# midipal-v03.net
KiCad netlist of a schematic drawn in EAGLE
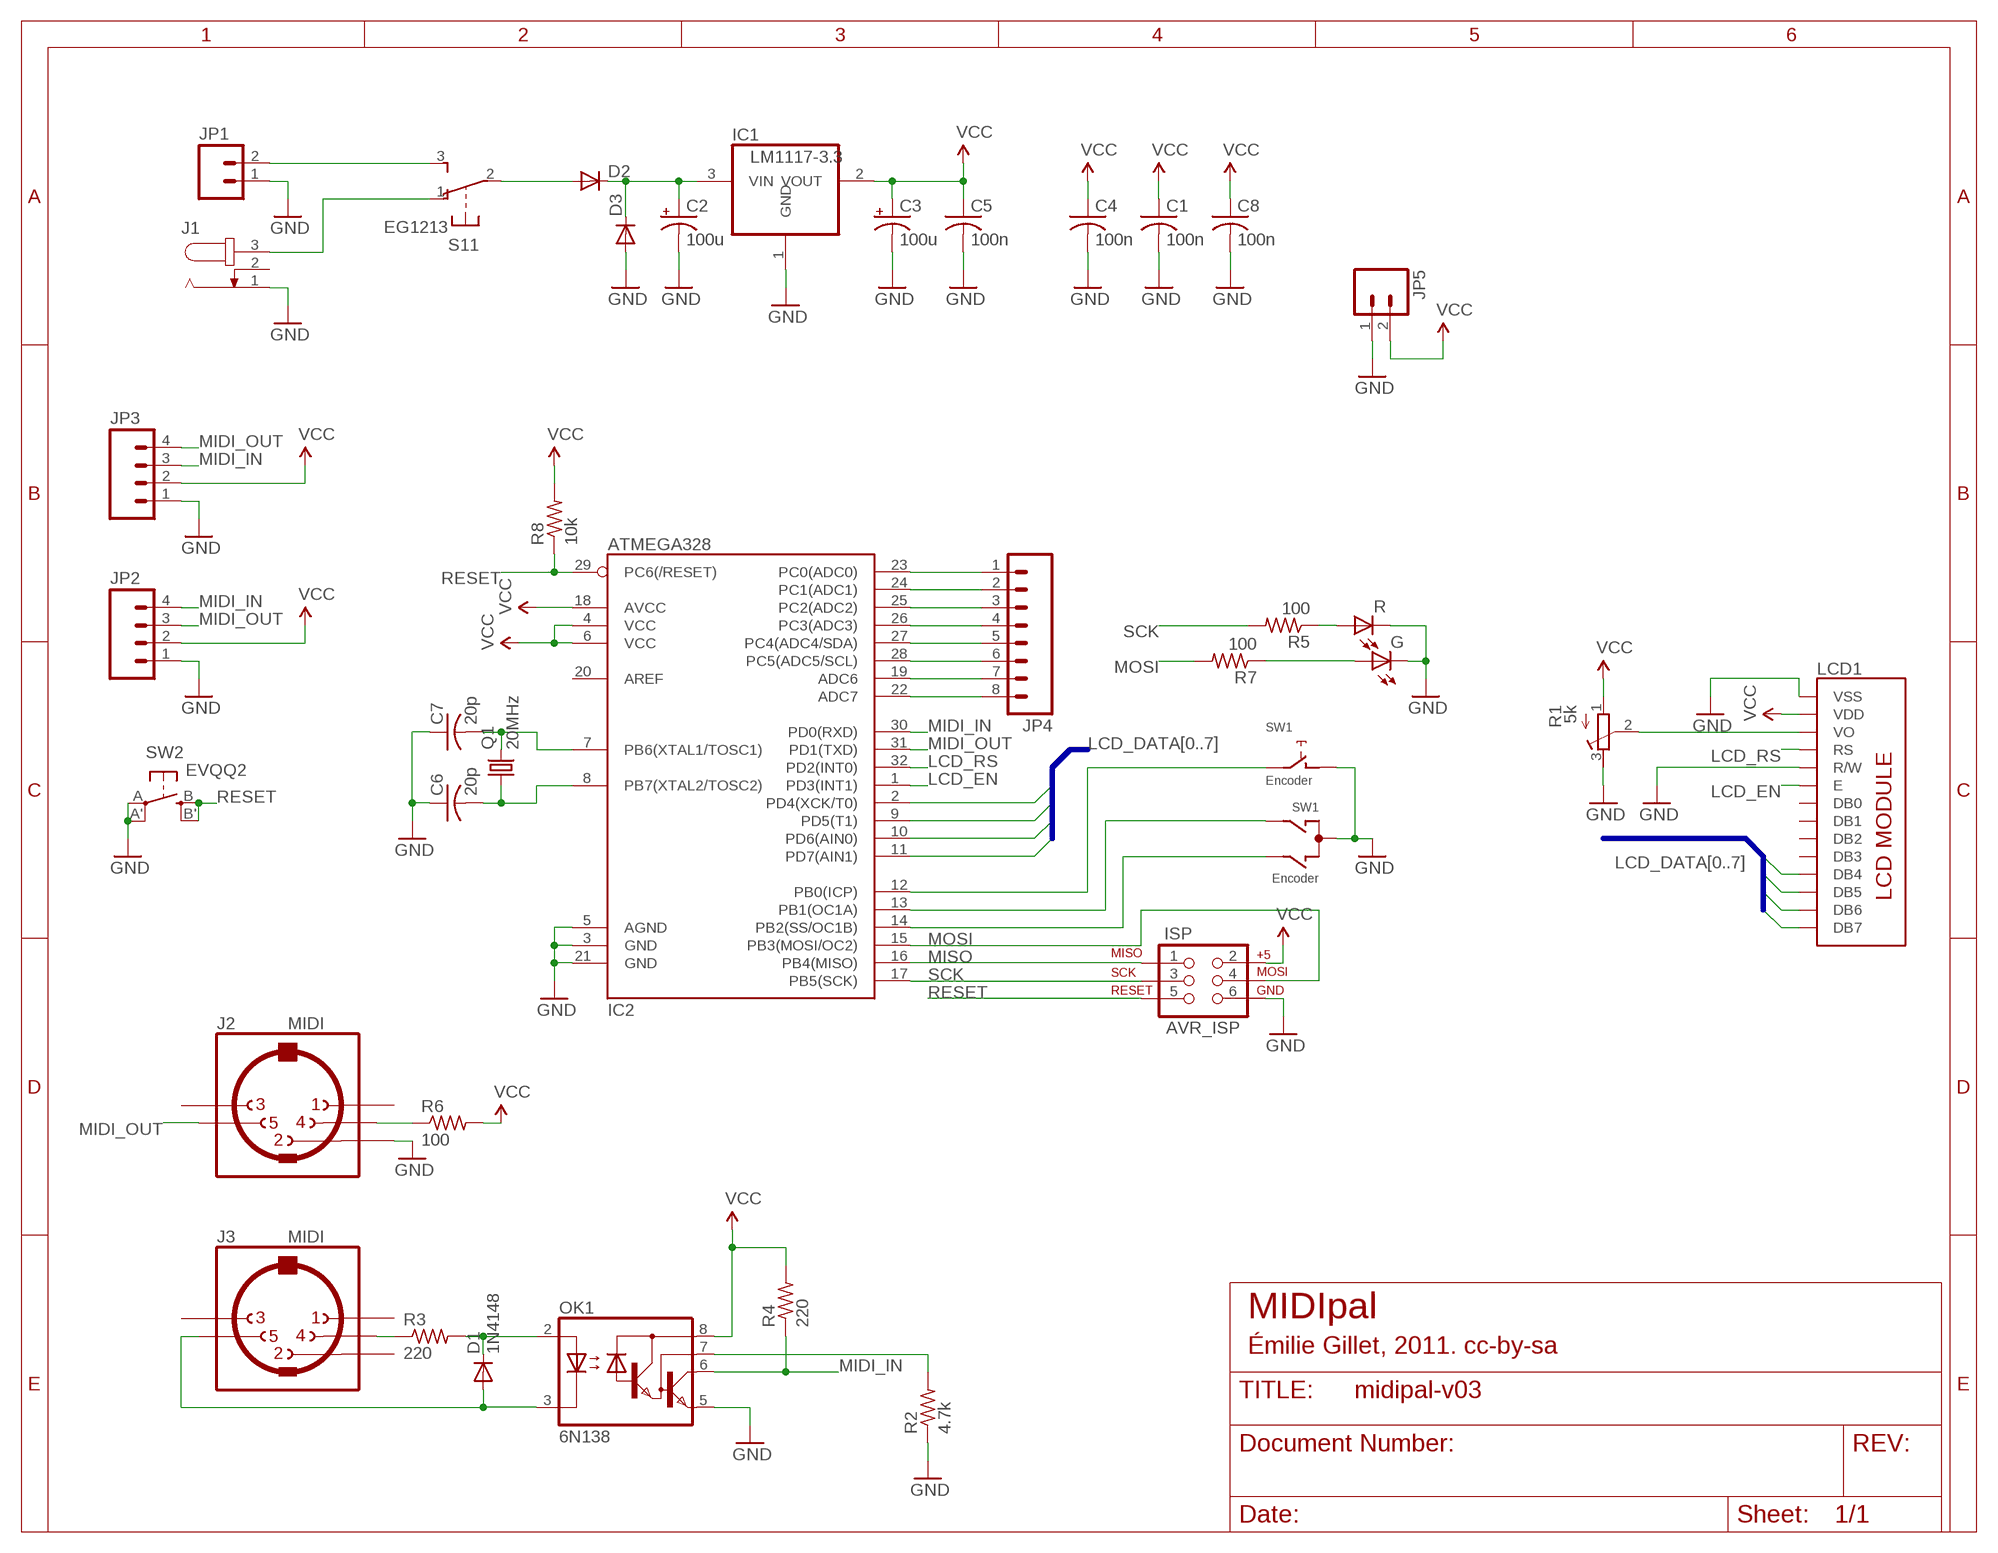
[diagram p0: schematic, sheet 1]

(export (version "E")
  (design (tool "Eeschema 10.0.6"))
  (components
    (comp (ref "C1")
      (value "100n")
      (footprint "eagle-import:C0805")
      (libsource (lib "eagle-import") (part "C-USC0805"))
    )
    (comp (ref "C2")
      (value "100u")
      (footprint "eagle-import:PANASONIC_D")
      (libsource (lib "eagle-import") (part "CPOL-USD"))
    )
    (comp (ref "C3")
      (value "100u")
      (footprint "eagle-import:PANASONIC_D")
      (libsource (lib "eagle-import") (part "CPOL-USD"))
    )
    (comp (ref "C4")
      (value "100n")
      (footprint "eagle-import:C0805")
      (libsource (lib "eagle-import") (part "C-USC0805"))
    )
    (comp (ref "C5")
      (value "100n")
      (footprint "eagle-import:C0805")
      (libsource (lib "eagle-import") (part "C-USC0805"))
    )
    (comp (ref "C6")
      (value "20p")
      (footprint "eagle-import:C0805")
      (libsource (lib "eagle-import") (part "C-USC0805"))
    )
    (comp (ref "C7")
      (value "20p")
      (footprint "eagle-import:C0805")
      (libsource (lib "eagle-import") (part "C-USC0805"))
    )
    (comp (ref "C8")
      (value "100n")
      (footprint "eagle-import:C0805")
      (libsource (lib "eagle-import") (part "C-USC0805"))
    )
    (comp (ref "D1")
      (value "1N4148")
      (footprint "eagle-import:SOD323-W")
      (libsource (lib "eagle-import") (part "DIODE-SOD323-W"))
    )
    (comp (ref "D2")
      (value "DIODESMB")
      (footprint "eagle-import:SMB-DIODE")
      (libsource (lib "eagle-import") (part "DIODESMB"))
    )
    (comp (ref "D3")
      (value "DIODESMB")
      (footprint "eagle-import:SMB-DIODE")
      (libsource (lib "eagle-import") (part "DIODESMB"))
    )
    (comp (ref "G")
      (value "LEDCHIPLED_1206")
      (footprint "eagle-import:CHIPLED_1206")
      (libsource (lib "eagle-import") (part "LEDCHIPLED_1206"))
    )
    (comp (ref "IC1")
      (value "LM1117-3.3")
      (footprint "eagle-import:SOT223")
      (libsource (lib "eagle-import") (part "REG1117"))
    )
    (comp (ref "IC2")
      (value "ATMEGA328")
      (footprint "eagle-import:TQFP32-08")
      (libsource (lib "eagle-import") (part "ATMEGA168"))
    )
    (comp (ref "ISP")
      (value "AVR_ISP")
      (footprint "eagle-import:2X3")
      (libsource (lib "eagle-import") (part "AVR_SPI_PRG_6PTH"))
    )
    (comp (ref "J1")
      (value "JACK-PLUG2")
      (footprint "eagle-import:SPC4078_BIG_HOLES")
      (libsource (lib "eagle-import") (part "JACK-PLUG2"))
    )
    (comp (ref "J2")
      (value "MIDI")
      (footprint "eagle-import:MAB5SH")
      (libsource (lib "eagle-import") (part "MAB5SH"))
    )
    (comp (ref "J3")
      (value "MIDI")
      (footprint "eagle-import:MAB5SH")
      (libsource (lib "eagle-import") (part "MAB5SH"))
    )
    (comp (ref "JP1")
      (value "M02")
      (footprint "eagle-import:1X02_LONGPADS")
      (libsource (lib "eagle-import") (part "M02"))
    )
    (comp (ref "JP2")
      (value "M04PTH")
      (footprint "eagle-import:1X04")
      (libsource (lib "eagle-import") (part "M04PTH"))
    )
    (comp (ref "JP3")
      (value "M04PTH")
      (footprint "eagle-import:1X04")
      (libsource (lib "eagle-import") (part "M04PTH"))
    )
    (comp (ref "JP4")
      (value "M08")
      (footprint "eagle-import:1X08")
      (libsource (lib "eagle-import") (part "M08"))
    )
    (comp (ref "JP5")
      (value "M02PTH")
      (footprint "eagle-import:1X02")
      (libsource (lib "eagle-import") (part "M02PTH"))
    )
    (comp (ref "LCD1")
      (value "LCD_MODULE_NO_BKL")
      (footprint "eagle-import:LCD_MODULE_1X8")
      (libsource (lib "eagle-import") (part "LCD_MODULE_NO_BKL"))
    )
    (comp (ref "OK1")
      (value "6N138")
      (footprint "eagle-import:DIL8-SMD")
      (libsource (lib "eagle-import") (part "6N138SMD8"))
    )
    (comp (ref "Q1")
      (value "20MHz")
      (footprint "eagle-import:HC49UP")
      (libsource (lib "eagle-import") (part "CRYSTALHC49UP"))
    )
    (comp (ref "R")
      (value "LEDCHIPLED_1206")
      (footprint "eagle-import:CHIPLED_1206")
      (libsource (lib "eagle-import") (part "LEDCHIPLED_1206"))
    )
    (comp (ref "R1")
      (value "5k")
      (footprint "eagle-import:RTRIM3296P")
      (libsource (lib "eagle-import") (part "R-TRIMM3296P"))
    )
    (comp (ref "R2")
      (value "4.7k")
      (footprint "eagle-import:M0805")
      (libsource (lib "eagle-import") (part "R-US_M0805"))
    )
    (comp (ref "R3")
      (value "220")
      (footprint "eagle-import:M0805")
      (libsource (lib "eagle-import") (part "R-US_M0805"))
    )
    (comp (ref "R4")
      (value "220")
      (footprint "eagle-import:R0805")
      (libsource (lib "eagle-import") (part "R-US_R0805"))
    )
    (comp (ref "R5")
      (value "100")
      (footprint "eagle-import:R0805")
      (libsource (lib "eagle-import") (part "R-US_R0805"))
    )
    (comp (ref "R6")
      (value "100")
      (footprint "eagle-import:R0805")
      (libsource (lib "eagle-import") (part "R-US_R0805"))
    )
    (comp (ref "R7")
      (value "100")
      (footprint "eagle-import:R0805")
      (libsource (lib "eagle-import") (part "R-US_R0805"))
    )
    (comp (ref "R8")
      (value "10k")
      (footprint "eagle-import:R0805")
      (libsource (lib "eagle-import") (part "R-US_R0805"))
    )
    (comp (ref "S1")
      (value "EG1213")
      (footprint "eagle-import:EG1213")
      (libsource (lib "eagle-import") (part "EG1213"))
    )
    (comp (ref "SW1")
      (value "Encoder")
      (footprint "eagle-import:ALPS_EC12E_SW")
      (libsource (lib "eagle-import") (part "EC12E_SW"))
    )
    (comp (ref "SW2")
      (value "EVQQ2")
      (footprint "eagle-import:EVQ-Q2")
      (libsource (lib "eagle-import") (part "EVQQ2"))
    )
  )
  (nets
    (net (code "5") (name "/LCD_DATA4") (class "Default")
      (node (ref "IC2") (pin "2") (pinfunction "PD4(XCK/T0)_2") (pintype "bidirectional"))
      (node (ref "LCD1") (pin "11") (pinfunction "DB4_11") (pintype "bidirectional"))
    )
    (net (code "6") (name "/LCD_DATA5") (class "Default")
      (node (ref "IC2") (pin "9") (pinfunction "PD5(T1)_9") (pintype "bidirectional"))
      (node (ref "LCD1") (pin "12") (pinfunction "DB5_12") (pintype "bidirectional"))
    )
    (net (code "7") (name "/LCD_DATA6") (class "Default")
      (node (ref "IC2") (pin "10") (pinfunction "PD6(AIN0)_10") (pintype "bidirectional"))
      (node (ref "LCD1") (pin "13") (pinfunction "DB6_13") (pintype "bidirectional"))
    )
    (net (code "8") (name "/LCD_DATA7") (class "Default")
      (node (ref "IC2") (pin "11") (pinfunction "PD7(AIN1)_11") (pintype "bidirectional"))
      (node (ref "LCD1") (pin "14") (pinfunction "DB7_14") (pintype "bidirectional"))
    )
    (net (code "10") (name "/LCD_EN") (class "Default")
      (node (ref "IC2") (pin "1") (pinfunction "PD3(INT1)_1") (pintype "bidirectional"))
      (node (ref "LCD1") (pin "6") (pinfunction "E_6") (pintype "input"))
    )
    (net (code "11") (name "/LCD_RS") (class "Default")
      (node (ref "IC2") (pin "32") (pinfunction "PD2(INT0)_32") (pintype "bidirectional"))
      (node (ref "LCD1") (pin "4") (pinfunction "RS_4") (pintype "input"))
    )
    (net (code "12") (name "/MIDI_IN") (class "Default")
      (node (ref "IC2") (pin "30") (pinfunction "PD0(RXD)_30") (pintype "bidirectional"))
      (node (ref "JP2") (pin "4") (pinfunction "4_4") (pintype "passive"))
      (node (ref "JP3") (pin "3") (pinfunction "3_3") (pintype "passive"))
      (node (ref "OK1") (pin "6") (pinfunction "VO_6") (pintype "passive"))
      (node (ref "R4") (pin "1") (pinfunction "1_1") (pintype "passive"))
    )
    (net (code "13") (name "/MIDI_OUT") (class "Default")
      (node (ref "IC2") (pin "31") (pinfunction "PD1(TXD)_31") (pintype "bidirectional"))
      (node (ref "J2") (pin "5") (pinfunction "5_5") (pintype "passive"))
      (node (ref "JP2") (pin "3") (pinfunction "3_3") (pintype "passive"))
      (node (ref "JP3") (pin "4") (pinfunction "4_4") (pintype "passive"))
    )
    (net (code "14") (name "/MISO") (class "Default")
      (node (ref "IC2") (pin "16") (pinfunction "PB4(MISO)_16") (pintype "bidirectional"))
      (node (ref "ISP") (pin "1") (pinfunction "1_1") (pintype "passive"))
    )
    (net (code "15") (name "/MOSI") (class "Default")
      (node (ref "IC2") (pin "15") (pinfunction "PB3(MOSI/OC2)_15") (pintype "bidirectional"))
      (node (ref "ISP") (pin "4") (pinfunction "4_4") (pintype "passive"))
      (node (ref "R7") (pin "2") (pinfunction "2_2") (pintype "passive"))
    )
    (net (code "16") (name "/RESET") (class "Default")
      (node (ref "IC2") (pin "29") (pinfunction "PC6(/RESET)_29") (pintype "bidirectional"))
      (node (ref "ISP") (pin "5") (pinfunction "5_5") (pintype "passive"))
      (node (ref "R8") (pin "1") (pinfunction "1_1") (pintype "passive"))
      (node (ref "SW2") (pin "B") (pinfunction "S_B") (pintype "passive"))
      (node (ref "SW2") (pin "B'") (pinfunction "S1_B'") (pintype "passive"))
    )
    (net (code "17") (name "/SCK") (class "Default")
      (node (ref "IC2") (pin "17") (pinfunction "PB5(SCK)_17") (pintype "bidirectional"))
      (node (ref "ISP") (pin "3") (pinfunction "3_3") (pintype "passive"))
      (node (ref "R5") (pin "2") (pinfunction "2_2") (pintype "passive"))
    )
    (net (code "18") (name "GND") (class "Default")
      (node (ref "C1") (pin "2") (pinfunction "2_2") (pintype "passive"))
      (node (ref "C2") (pin "-") (pinfunction "-_-") (pintype "passive"))
      (node (ref "C3") (pin "-") (pinfunction "-_-") (pintype "passive"))
      (node (ref "C4") (pin "2") (pinfunction "2_2") (pintype "passive"))
      (node (ref "C5") (pin "2") (pinfunction "2_2") (pintype "passive"))
      (node (ref "C6") (pin "1") (pinfunction "1_1") (pintype "passive"))
      (node (ref "C7") (pin "1") (pinfunction "1_1") (pintype "passive"))
      (node (ref "C8") (pin "2") (pinfunction "2_2") (pintype "passive"))
      (node (ref "D3") (pin "A") (pinfunction "A_A") (pintype "passive"))
      (node (ref "G") (pin "C") (pinfunction "C_C") (pintype "passive"))
      (node (ref "IC1") (pin "1") (pinfunction "GND_1") (pintype "power_in"))
      (node (ref "IC2") (pin "21") (pinfunction "GND_21") (pintype "bidirectional"))
      (node (ref "IC2") (pin "3") (pinfunction "GND_3") (pintype "bidirectional"))
      (node (ref "IC2") (pin "5") (pinfunction "AGND_5") (pintype "bidirectional"))
      (node (ref "ISP") (pin "6") (pinfunction "6_6") (pintype "passive"))
      (node (ref "J1") (pin "1") (pinfunction "1_1") (pintype "passive"))
      (node (ref "J2") (pin "2") (pinfunction "2_2") (pintype "passive"))
      (node (ref "JP1") (pin "1") (pinfunction "1_1") (pintype "passive"))
      (node (ref "JP2") (pin "1") (pinfunction "1_1") (pintype "passive"))
      (node (ref "JP3") (pin "1") (pinfunction "1_1") (pintype "passive"))
      (node (ref "JP5") (pin "1") (pinfunction "1_1") (pintype "passive"))
      (node (ref "LCD1") (pin "1") (pinfunction "VSS_1") (pintype "power_in"))
      (node (ref "LCD1") (pin "5") (pinfunction "R/W_5") (pintype "input"))
      (node (ref "OK1") (pin "5") (pinfunction "GND_5") (pintype "passive"))
      (node (ref "R") (pin "C") (pinfunction "C_C") (pintype "passive"))
      (node (ref "R1") (pin "3") (pinfunction "A_3") (pintype "passive"))
      (node (ref "R2") (pin "1") (pinfunction "1_1") (pintype "passive"))
      (node (ref "SW1") (pin "C") (pinfunction "C_C") (pintype "passive"))
      (node (ref "SW1") (pin "D") (pinfunction "1_D") (pintype "passive"))
      (node (ref "SW2") (pin "A") (pinfunction "P_A") (pintype "passive"))
      (node (ref "SW2") (pin "A'") (pinfunction "P1_A'") (pintype "passive"))
    )
    (net (code "19") (name "Net-(G-PadA)") (class "Default")
      (node (ref "G") (pin "A") (pinfunction "A_A") (pintype "passive"))
      (node (ref "R7") (pin "1") (pinfunction "1_1") (pintype "passive"))
    )
    (net (code "20") (name "Net-(IC1-VIN)") (class "Default")
      (node (ref "C2") (pin "+") (pinfunction "+_+") (pintype "passive"))
      (node (ref "D2") (pin "C") (pinfunction "C_C") (pintype "passive"))
      (node (ref "D3") (pin "C") (pinfunction "C_C") (pintype "passive"))
      (node (ref "IC1") (pin "3") (pinfunction "VIN_3") (pintype "input"))
    )
    (net (code "21") (name "Net-(IC2-ADC6)") (class "Default")
      (node (ref "IC2") (pin "19") (pinfunction "ADC6_19") (pintype "bidirectional"))
      (node (ref "JP4") (pin "7") (pinfunction "7_7") (pintype "passive"))
    )
    (net (code "22") (name "Net-(IC2-ADC7)") (class "Default")
      (node (ref "IC2") (pin "22") (pinfunction "ADC7_22") (pintype "bidirectional"))
      (node (ref "JP4") (pin "8") (pinfunction "8_8") (pintype "passive"))
    )
    (net (code "23") (name "Net-(IC2-PB0(ICP))") (class "Default")
      (node (ref "IC2") (pin "12") (pinfunction "PB0(ICP)_12") (pintype "bidirectional"))
      (node (ref "SW1") (pin "E") (pinfunction "2_E") (pintype "passive"))
    )
    (net (code "24") (name "Net-(IC2-PB1(OC1A))") (class "Default")
      (node (ref "IC2") (pin "13") (pinfunction "PB1(OC1A)_13") (pintype "bidirectional"))
      (node (ref "SW1") (pin "A") (pinfunction "A_A") (pintype "passive"))
    )
    (net (code "25") (name "Net-(IC2-PB2(SS{slash}OC1B))") (class "Default")
      (node (ref "IC2") (pin "14") (pinfunction "PB2(SS/OC1B)_14") (pintype "bidirectional"))
      (node (ref "SW1") (pin "B") (pinfunction "B_B") (pintype "passive"))
    )
    (net (code "26") (name "Net-(IC2-PB6(XTAL1{slash}TOSC1))") (class "Default")
      (node (ref "C7") (pin "2") (pinfunction "2_2") (pintype "passive"))
      (node (ref "IC2") (pin "7") (pinfunction "PB6(XTAL1/TOSC1)_7") (pintype "bidirectional"))
      (node (ref "Q1") (pin "2") (pinfunction "2_2") (pintype "passive"))
    )
    (net (code "27") (name "Net-(IC2-PB7(XTAL2{slash}TOSC2))") (class "Default")
      (node (ref "C6") (pin "2") (pinfunction "2_2") (pintype "passive"))
      (node (ref "IC2") (pin "8") (pinfunction "PB7(XTAL2/TOSC2)_8") (pintype "bidirectional"))
      (node (ref "Q1") (pin "1") (pinfunction "1_1") (pintype "passive"))
    )
    (net (code "28") (name "Net-(IC2-PC0(ADC0))") (class "Default")
      (node (ref "IC2") (pin "23") (pinfunction "PC0(ADC0)_23") (pintype "bidirectional"))
      (node (ref "JP4") (pin "1") (pinfunction "1_1") (pintype "passive"))
    )
    (net (code "29") (name "Net-(IC2-PC1(ADC1))") (class "Default")
      (node (ref "IC2") (pin "24") (pinfunction "PC1(ADC1)_24") (pintype "bidirectional"))
      (node (ref "JP4") (pin "2") (pinfunction "2_2") (pintype "passive"))
    )
    (net (code "30") (name "Net-(IC2-PC2(ADC2))") (class "Default")
      (node (ref "IC2") (pin "25") (pinfunction "PC2(ADC2)_25") (pintype "bidirectional"))
      (node (ref "JP4") (pin "3") (pinfunction "3_3") (pintype "passive"))
    )
    (net (code "31") (name "Net-(IC2-PC3(ADC3))") (class "Default")
      (node (ref "IC2") (pin "26") (pinfunction "PC3(ADC3)_26") (pintype "bidirectional"))
      (node (ref "JP4") (pin "4") (pinfunction "4_4") (pintype "passive"))
    )
    (net (code "32") (name "Net-(IC2-PC4(ADC4{slash}SDA))") (class "Default")
      (node (ref "IC2") (pin "27") (pinfunction "PC4(ADC4/SDA)_27") (pintype "bidirectional"))
      (node (ref "JP4") (pin "5") (pinfunction "5_5") (pintype "passive"))
    )
    (net (code "33") (name "Net-(IC2-PC5(ADC5{slash}SCL))") (class "Default")
      (node (ref "IC2") (pin "28") (pinfunction "PC5(ADC5/SCL)_28") (pintype "bidirectional"))
      (node (ref "JP4") (pin "6") (pinfunction "6_6") (pintype "passive"))
    )
    (net (code "34") (name "Net-(J2-Pad4)") (class "Default")
      (node (ref "J2") (pin "4") (pinfunction "4_4") (pintype "passive"))
      (node (ref "R6") (pin "1") (pinfunction "1_1") (pintype "passive"))
    )
    (net (code "35") (name "Net-(J3-Pad4)") (class "Default")
      (node (ref "J3") (pin "4") (pinfunction "4_4") (pintype "passive"))
      (node (ref "R3") (pin "1") (pinfunction "1_1") (pintype "passive"))
    )
    (net (code "36") (name "Net-(LCD1-VO)") (class "Default")
      (node (ref "LCD1") (pin "3") (pinfunction "VO_3") (pintype "bidirectional"))
      (node (ref "R1") (pin "2") (pinfunction "S_2") (pintype "passive"))
    )
    (net (code "37") (name "Net-(OK1-A)") (class "Default")
      (node (ref "D1") (pin "C") (pinfunction "C_C") (pintype "passive"))
      (node (ref "OK1") (pin "2") (pinfunction "A_2") (pintype "passive"))
      (node (ref "R3") (pin "2") (pinfunction "2_2") (pintype "passive"))
    )
    (net (code "38") (name "Net-(OK1-C)") (class "Default")
      (node (ref "D1") (pin "A") (pinfunction "A_A") (pintype "passive"))
      (node (ref "J3") (pin "5") (pinfunction "5_5") (pintype "passive"))
      (node (ref "OK1") (pin "3") (pinfunction "C_3") (pintype "passive"))
    )
    (net (code "39") (name "Net-(OK1-VB)") (class "Default")
      (node (ref "OK1") (pin "7") (pinfunction "VB_7") (pintype "passive"))
      (node (ref "R2") (pin "2") (pinfunction "2_2") (pintype "passive"))
    )
    (net (code "40") (name "Net-(R-PadA)") (class "Default")
      (node (ref "R") (pin "A") (pinfunction "A_A") (pintype "passive"))
      (node (ref "R5") (pin "1") (pinfunction "1_1") (pintype "passive"))
    )
    (net (code "41") (name "Net-(S1A-O)") (class "Default")
      (node (ref "J1") (pin "3") (pinfunction "3_3") (pintype "passive"))
      (node (ref "S1") (pin "1") (pinfunction "O_1") (pintype "passive"))
    )
    (net (code "42") (name "Net-(S1A-P)") (class "Default")
      (node (ref "D2") (pin "A") (pinfunction "A_A") (pintype "passive"))
      (node (ref "S1") (pin "2") (pinfunction "P_2") (pintype "passive"))
    )
    (net (code "43") (name "Net-(S1A-S)") (class "Default")
      (node (ref "JP1") (pin "2") (pinfunction "2_2") (pintype "passive"))
      (node (ref "S1") (pin "3") (pinfunction "S_3") (pintype "passive"))
    )
    (net (code "44") (name "VCC") (class "Default")
      (node (ref "C1") (pin "1") (pinfunction "1_1") (pintype "passive"))
      (node (ref "C3") (pin "+") (pinfunction "+_+") (pintype "passive"))
      (node (ref "C4") (pin "1") (pinfunction "1_1") (pintype "passive"))
      (node (ref "C5") (pin "1") (pinfunction "1_1") (pintype "passive"))
      (node (ref "C8") (pin "1") (pinfunction "1_1") (pintype "passive"))
      (node (ref "IC1") (pin "2") (pinfunction "VOUT_2") (pintype "output"))
      (node (ref "IC2") (pin "18") (pinfunction "AVCC_18") (pintype "bidirectional"))
      (node (ref "IC2") (pin "4") (pinfunction "VCC_4") (pintype "bidirectional"))
      (node (ref "IC2") (pin "6") (pinfunction "VCC_6") (pintype "bidirectional"))
      (node (ref "ISP") (pin "2") (pinfunction "2_2") (pintype "passive"))
      (node (ref "JP2") (pin "2") (pinfunction "2_2") (pintype "passive"))
      (node (ref "JP3") (pin "2") (pinfunction "2_2") (pintype "passive"))
      (node (ref "JP5") (pin "2") (pinfunction "2_2") (pintype "passive"))
      (node (ref "LCD1") (pin "2") (pinfunction "VDD_2") (pintype "power_in"))
      (node (ref "OK1") (pin "8") (pinfunction "VCC_8") (pintype "passive"))
      (node (ref "R1") (pin "1") (pinfunction "E_1") (pintype "passive"))
      (node (ref "R4") (pin "2") (pinfunction "2_2") (pintype "passive"))
      (node (ref "R6") (pin "2") (pinfunction "2_2") (pintype "passive"))
      (node (ref "R8") (pin "2") (pinfunction "2_2") (pintype "passive"))
    )
    (net (code "45") (name "unconnected-(IC2-AREF-Pad20)") (class "Default")
      (node (ref "IC2") (pin "20") (pinfunction "AREF_20") (pintype "bidirectional"))
    )
    (net (code "46") (name "unconnected-(J1-Pad2)") (class "Default")
      (node (ref "J1") (pin "2") (pinfunction "2_2") (pintype "passive"))
    )
    (net (code "47") (name "unconnected-(J2-Pad1)") (class "Default")
      (node (ref "J2") (pin "1") (pinfunction "1_1") (pintype "passive"))
    )
    (net (code "48") (name "unconnected-(J2-Pad3)") (class "Default")
      (node (ref "J2") (pin "3") (pinfunction "3_3") (pintype "passive"))
    )
    (net (code "49") (name "unconnected-(J3-Pad1)") (class "Default")
      (node (ref "J3") (pin "1") (pinfunction "1_1") (pintype "passive"))
    )
    (net (code "50") (name "unconnected-(J3-Pad2)") (class "Default")
      (node (ref "J3") (pin "2") (pinfunction "2_2") (pintype "passive"))
    )
    (net (code "51") (name "unconnected-(J3-Pad3)") (class "Default")
      (node (ref "J3") (pin "3") (pinfunction "3_3") (pintype "passive"))
    )
    (net (code "52") (name "unconnected-(LCD1-DB0-Pad7)") (class "Default")
      (node (ref "LCD1") (pin "7") (pinfunction "DB0_7") (pintype "bidirectional"))
    )
    (net (code "53") (name "unconnected-(LCD1-DB1-Pad8)") (class "Default")
      (node (ref "LCD1") (pin "8") (pinfunction "DB1_8") (pintype "bidirectional"))
    )
    (net (code "54") (name "unconnected-(LCD1-DB2-Pad9)") (class "Default")
      (node (ref "LCD1") (pin "9") (pinfunction "DB2_9") (pintype "bidirectional"))
    )
    (net (code "55") (name "unconnected-(LCD1-DB3-Pad10)") (class "Default")
      (node (ref "LCD1") (pin "10") (pinfunction "DB3_10") (pintype "bidirectional"))
    )
  )
)
